# Circuit_V0_1.net
KiCad netlist of a schematic drawn in EAGLE
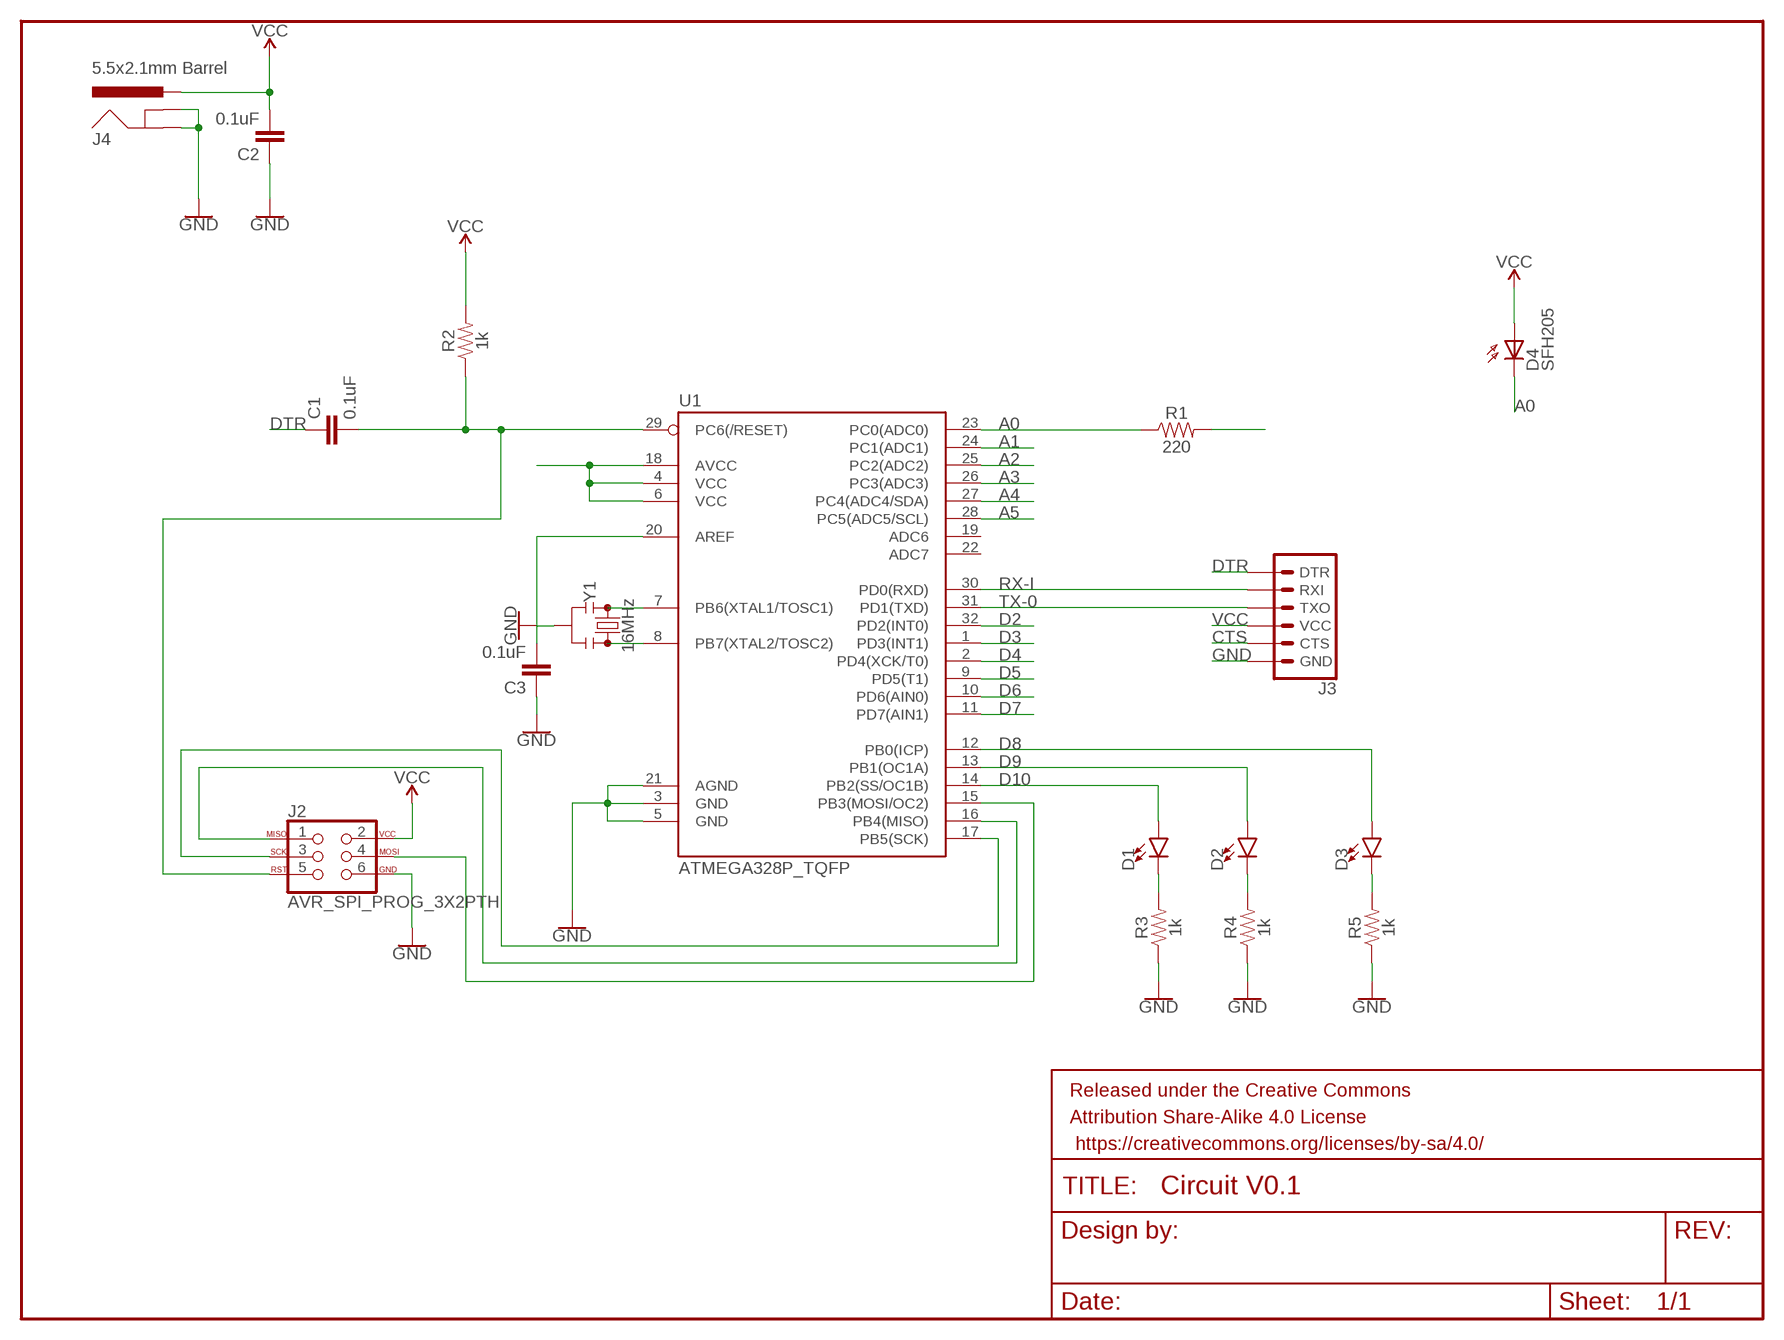
[diagram p0: schematic, sheet 1]

(export (version "E")
  (design (tool "Eeschema 10.0.6"))
  (components
    (comp (ref "C1")
      (value "0.1uF")
      (footprint "eagle-import:CAP-PTH-SMALL-KIT")
      (libsource (lib "eagle-import") (part "0.1UF-KIT-EZ-50V-20%"))
    )
    (comp (ref "C2")
      (value "0.1uF")
      (footprint "eagle-import:CAP-PTH-SMALL-KIT")
      (libsource (lib "eagle-import") (part "0.1UF-KIT-EZ-50V-20%"))
    )
    (comp (ref "C3")
      (value "0.1uF")
      (footprint "eagle-import:CAP-PTH-SMALL-KIT")
      (libsource (lib "eagle-import") (part "0.1UF-KIT-EZ-50V-20%"))
    )
    (comp (ref "D1")
      (value "LED5MM")
      (footprint "eagle-import:LED_5MM")
      (libsource (lib "eagle-import") (part "LED5MM"))
    )
    (comp (ref "D2")
      (value "LED5MM")
      (footprint "eagle-import:LED_5MM")
      (libsource (lib "eagle-import") (part "LED5MM"))
    )
    (comp (ref "D3")
      (value "LED5MM")
      (footprint "eagle-import:LED_5MM")
      (libsource (lib "eagle-import") (part "LED5MM"))
    )
    (comp (ref "D4")
      (value "SFH205")
      (footprint "eagle-import:SFH205")
      (libsource (lib "eagle-import") (part "SFH205"))
    )
    (comp (ref "FRAME1")
      (value "FRAME-LETTER")
      (footprint "eagle-import:CREATIVE_COMMONS")
      (libsource (lib "eagle-import") (part "FRAME-LETTER"))
    )
    (comp (ref "J2")
      (value "AVR_SPI_PROG_3X2PTH")
      (footprint "eagle-import:2X3")
      (libsource (lib "eagle-import") (part "AVR_SPI_PROG_3X2PTH"))
    )
    (comp (ref "J3")
      (value "6_PIN_SERIAL_TARGET")
      (footprint "eagle-import:1X06")
      (libsource (lib "eagle-import") (part "6_PIN_SERIAL_TARGET"))
    )
    (comp (ref "J4")
      (value "5.5x2.1mm Barrel")
      (footprint "eagle-import:POWER_JACK_SMD")
      (fields (field (name "SPICEPREFIX") "J"))
      (libsource (lib "eagle-import") (part "POWER_JACKSMD"))
    )
    (comp (ref "R1")
      (value "220")
      (footprint "eagle-import:0603")
      (libsource (lib "eagle-import") (part "220OHM-0603-1/10W-1%"))
    )
    (comp (ref "R2")
      (value "1k")
      (footprint "eagle-import:AXIAL-0.3-KIT")
      (libsource (lib "eagle-import") (part "RESISTORAXIAL-0.3-KIT"))
    )
    (comp (ref "R3")
      (value "1k")
      (footprint "eagle-import:AXIAL-0.3-KIT")
      (libsource (lib "eagle-import") (part "RESISTORAXIAL-0.3-KIT"))
    )
    (comp (ref "R4")
      (value "1k")
      (footprint "eagle-import:AXIAL-0.3-KIT")
      (libsource (lib "eagle-import") (part "RESISTORAXIAL-0.3-KIT"))
    )
    (comp (ref "R5")
      (value "1k")
      (footprint "eagle-import:AXIAL-0.3-KIT")
      (libsource (lib "eagle-import") (part "RESISTORAXIAL-0.3-KIT"))
    )
    (comp (ref "U1")
      (value "ATMEGA328P_TQFP")
      (footprint "eagle-import:TQFP32-08")
      (libsource (lib "eagle-import") (part "ATMEGA328P_TQFP"))
    )
    (comp (ref "Y1")
      (value "16MHz")
      (footprint "eagle-import:RESONATOR-SMD-3.2X1.3")
      (libsource (lib "eagle-import") (part "RESONATOR-16MHZSMD_3.2X1.3"))
    )
  )
  (nets
    (net (code "1") (name "/A0") (class "Default")
      (node (ref "D4") (pin "K") (pinfunction "C_K") (pintype "passive"))
      (node (ref "R1") (pin "1") (pinfunction "1_1") (pintype "passive"))
      (node (ref "U1") (pin "23") (pinfunction "PC0(ADC0)_23") (pintype "bidirectional"))
    )
    (net (code "2") (name "/A1") (class "Default")
      (node (ref "U1") (pin "24") (pinfunction "PC1(ADC1)_24") (pintype "bidirectional"))
    )
    (net (code "3") (name "/A2") (class "Default")
      (node (ref "U1") (pin "25") (pinfunction "PC2(ADC2)_25") (pintype "bidirectional"))
    )
    (net (code "4") (name "/A3") (class "Default")
      (node (ref "U1") (pin "26") (pinfunction "PC3(ADC3)_26") (pintype "bidirectional"))
    )
    (net (code "5") (name "/A4") (class "Default")
      (node (ref "U1") (pin "27") (pinfunction "PC4(ADC4/SDA)_27") (pintype "bidirectional"))
    )
    (net (code "6") (name "/A5") (class "Default")
      (node (ref "U1") (pin "28") (pinfunction "PC5(ADC5/SCL)_28") (pintype "bidirectional"))
    )
    (net (code "7") (name "/CTS") (class "Default")
      (node (ref "J3") (pin "5") (pinfunction "CTS_5") (pintype "passive"))
    )
    (net (code "8") (name "/D2") (class "Default")
      (node (ref "U1") (pin "32") (pinfunction "PD2(INT0)_32") (pintype "bidirectional"))
    )
    (net (code "9") (name "/D3") (class "Default")
      (node (ref "U1") (pin "1") (pinfunction "PD3(INT1)_1") (pintype "bidirectional"))
    )
    (net (code "10") (name "/D4") (class "Default")
      (node (ref "U1") (pin "2") (pinfunction "PD4(XCK/T0)_2") (pintype "bidirectional"))
    )
    (net (code "11") (name "/D5") (class "Default")
      (node (ref "U1") (pin "9") (pinfunction "PD5(T1)_9") (pintype "bidirectional"))
    )
    (net (code "12") (name "/D6") (class "Default")
      (node (ref "U1") (pin "10") (pinfunction "PD6(AIN0)_10") (pintype "bidirectional"))
    )
    (net (code "13") (name "/D7") (class "Default")
      (node (ref "U1") (pin "11") (pinfunction "PD7(AIN1)_11") (pintype "bidirectional"))
    )
    (net (code "14") (name "/D8") (class "Default")
      (node (ref "D3") (pin "A") (pinfunction "A_A") (pintype "passive"))
      (node (ref "U1") (pin "12") (pinfunction "PB0(ICP)_12") (pintype "bidirectional"))
    )
    (net (code "15") (name "/D9") (class "Default")
      (node (ref "D2") (pin "A") (pinfunction "A_A") (pintype "passive"))
      (node (ref "U1") (pin "13") (pinfunction "PB1(OC1A)_13") (pintype "bidirectional"))
    )
    (net (code "16") (name "/D10") (class "Default")
      (node (ref "D1") (pin "A") (pinfunction "A_A") (pintype "passive"))
      (node (ref "U1") (pin "14") (pinfunction "PB2(SS/OC1B)_14") (pintype "bidirectional"))
    )
    (net (code "17") (name "/DTR") (class "Default")
      (node (ref "C1") (pin "1") (pinfunction "1_1") (pintype "passive"))
      (node (ref "J3") (pin "1") (pinfunction "DTR_1") (pintype "passive"))
    )
    (net (code "18") (name "/RX-I") (class "Default")
      (node (ref "J3") (pin "2") (pinfunction "RXI_2") (pintype "passive"))
      (node (ref "U1") (pin "30") (pinfunction "PD0(RXD)_30") (pintype "bidirectional"))
    )
    (net (code "19") (name "/TX-0") (class "Default")
      (node (ref "J3") (pin "3") (pinfunction "TXO_3") (pintype "passive"))
      (node (ref "U1") (pin "31") (pinfunction "PD1(TXD)_31") (pintype "bidirectional"))
    )
    (net (code "20") (name "GND") (class "Default")
      (node (ref "C2") (pin "1") (pinfunction "1_1") (pintype "passive"))
      (node (ref "C3") (pin "1") (pinfunction "1_1") (pintype "passive"))
      (node (ref "J2") (pin "6") (pinfunction "6_6") (pintype "passive"))
      (node (ref "J3") (pin "6") (pinfunction "GND_6") (pintype "passive"))
      (node (ref "J4") (pin "GND") (pinfunction "GNDBREAK_GND") (pintype "bidirectional"))
      (node (ref "J4") (pin "P$4") (pinfunction "GND_P$4") (pintype "bidirectional"))
      (node (ref "R3") (pin "P$1") (pinfunction "1_P$1") (pintype "passive"))
      (node (ref "R4") (pin "P$1") (pinfunction "1_P$1") (pintype "passive"))
      (node (ref "R5") (pin "P$1") (pinfunction "1_P$1") (pintype "passive"))
      (node (ref "U1") (pin "21") (pinfunction "AGND_21") (pintype "bidirectional"))
      (node (ref "U1") (pin "3") (pinfunction "GND_3") (pintype "bidirectional"))
      (node (ref "U1") (pin "5") (pinfunction "GND_5") (pintype "bidirectional"))
      (node (ref "Y1") (pin "2") (pinfunction "2_2") (pintype "passive"))
    )
    (net (code "21") (name "Net-(D1-C)") (class "Default")
      (node (ref "D1") (pin "K") (pinfunction "C_K") (pintype "passive"))
      (node (ref "R3") (pin "P$2") (pinfunction "2_P$2") (pintype "passive"))
    )
    (net (code "22") (name "Net-(D2-C)") (class "Default")
      (node (ref "D2") (pin "K") (pinfunction "C_K") (pintype "passive"))
      (node (ref "R4") (pin "P$2") (pinfunction "2_P$2") (pintype "passive"))
    )
    (net (code "23") (name "Net-(D3-C)") (class "Default")
      (node (ref "D3") (pin "K") (pinfunction "C_K") (pintype "passive"))
      (node (ref "R5") (pin "P$2") (pinfunction "2_P$2") (pintype "passive"))
    )
    (net (code "24") (name "Net-(R2-1)") (class "Default")
      (node (ref "C1") (pin "2") (pinfunction "2_2") (pintype "passive"))
      (node (ref "J2") (pin "5") (pinfunction "5_5") (pintype "passive"))
      (node (ref "R2") (pin "P$1") (pinfunction "1_P$1") (pintype "passive"))
      (node (ref "U1") (pin "29") (pinfunction "PC6(/RESET)_29") (pintype "bidirectional"))
    )
    (net (code "25") (name "Net-(U1-AREF)") (class "Default")
      (node (ref "C3") (pin "2") (pinfunction "2_2") (pintype "passive"))
      (node (ref "U1") (pin "20") (pinfunction "AREF_20") (pintype "bidirectional"))
    )
    (net (code "26") (name "Net-(U1-AVCC)") (class "Default")
      (node (ref "U1") (pin "18") (pinfunction "AVCC_18") (pintype "bidirectional"))
      (node (ref "U1") (pin "4") (pinfunction "VCC_4") (pintype "bidirectional"))
      (node (ref "U1") (pin "6") (pinfunction "VCC_6") (pintype "bidirectional"))
    )
    (net (code "27") (name "Net-(U1-PB3(MOSI{slash}OC2))") (class "Default")
      (node (ref "J2") (pin "4") (pinfunction "4_4") (pintype "passive"))
      (node (ref "U1") (pin "15") (pinfunction "PB3(MOSI/OC2)_15") (pintype "bidirectional"))
    )
    (net (code "28") (name "Net-(U1-PB4(MISO))") (class "Default")
      (node (ref "J2") (pin "1") (pinfunction "1_1") (pintype "passive"))
      (node (ref "U1") (pin "16") (pinfunction "PB4(MISO)_16") (pintype "bidirectional"))
    )
    (net (code "29") (name "Net-(U1-PB5(SCK))") (class "Default")
      (node (ref "J2") (pin "3") (pinfunction "3_3") (pintype "passive"))
      (node (ref "U1") (pin "17") (pinfunction "PB5(SCK)_17") (pintype "bidirectional"))
    )
    (net (code "30") (name "Net-(U1-PB6(XTAL1{slash}TOSC1))") (class "Default")
      (node (ref "U1") (pin "7") (pinfunction "PB6(XTAL1/TOSC1)_7") (pintype "bidirectional"))
      (node (ref "Y1") (pin "1") (pinfunction "1_1") (pintype "passive"))
    )
    (net (code "31") (name "Net-(U1-PB7(XTAL2{slash}TOSC2))") (class "Default")
      (node (ref "U1") (pin "8") (pinfunction "PB7(XTAL2/TOSC2)_8") (pintype "bidirectional"))
      (node (ref "Y1") (pin "3") (pinfunction "3_3") (pintype "passive"))
    )
    (net (code "32") (name "VCC") (class "Default")
      (node (ref "C2") (pin "2") (pinfunction "2_2") (pintype "passive"))
      (node (ref "D4") (pin "A") (pinfunction "A_A") (pintype "passive"))
      (node (ref "J2") (pin "2") (pinfunction "2_2") (pintype "passive"))
      (node (ref "J3") (pin "4") (pinfunction "VCC_4") (pintype "passive"))
      (node (ref "J4") (pin "VIN0") (pinfunction "PWR_VIN0") (pintype "bidirectional"))
      (node (ref "R2") (pin "P$2") (pinfunction "2_P$2") (pintype "passive"))
    )
    (net (code "33") (name "unconnected-(R1-Pad2)") (class "Default")
      (node (ref "R1") (pin "2") (pinfunction "2_2") (pintype "passive"))
    )
    (net (code "34") (name "unconnected-(U1-ADC6-Pad19)") (class "Default")
      (node (ref "U1") (pin "19") (pinfunction "ADC6_19") (pintype "bidirectional"))
    )
    (net (code "35") (name "unconnected-(U1-ADC7-Pad22)") (class "Default")
      (node (ref "U1") (pin "22") (pinfunction "ADC7_22") (pintype "bidirectional"))
    )
  )
)
